# pixracer_power.net
KiCad netlist of a schematic drawn in Altium Designer
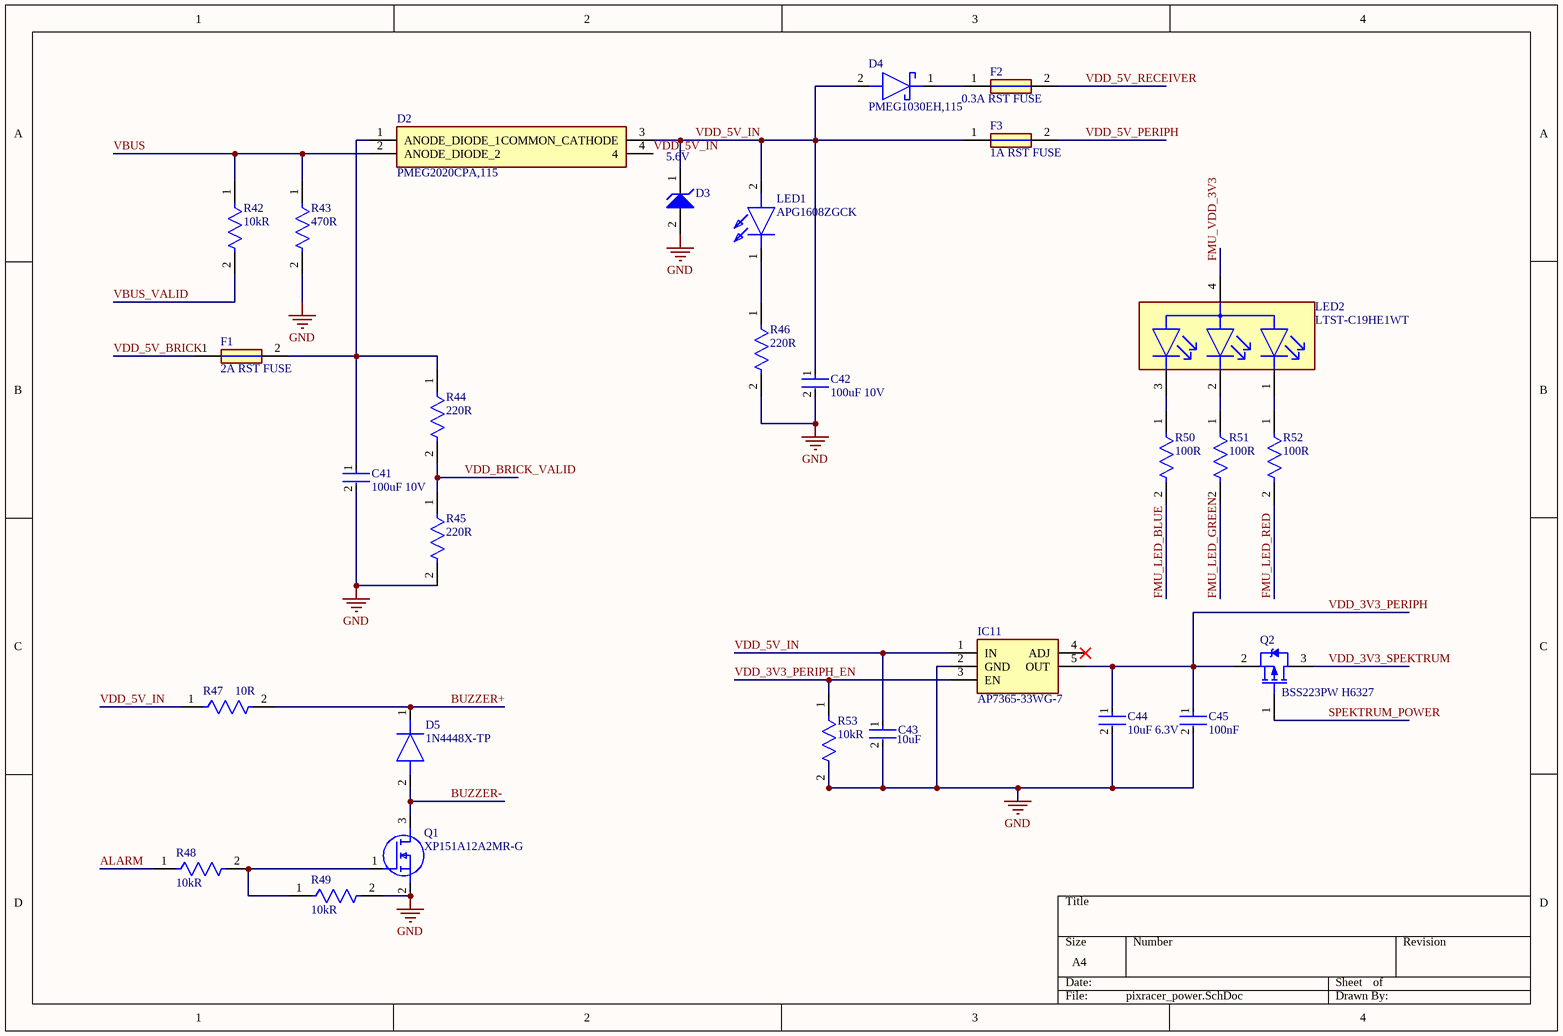
[diagram p0: pixracer_power.SchDoc]

(export (version "E")
  (design (tool "Eeschema 10.0.6"))
  (components
    (comp (ref "C41")
      (value "C3216X5R1A107M160AC")
      (footprint "FP-C3216-160-0_3-IPC_C")
      (description "Multilayer Ceramic Capacitors 100uF ±20% 10V X5R SMD 1206")
      (fields
        (field (name "CAPACITANCE") "100uF 10V")
        (field (name "VOLTAGE") "10V")
        (field (name "TOLERANCE") "20%")
      )
      (libsource (lib "Altium Content Vault") (part "02cd4be3c70576c341d710602a673aa"))
    )
    (comp (ref "C42")
      (value "C3216X5R1A107M160AC")
      (footprint "FP-C3216-160-0_3-IPC_C")
      (description "Multilayer Ceramic Capacitors 100uF ±20% 10V X5R SMD 1206")
      (fields
        (field (name "CAPACITANCE") "100uF 10V")
        (field (name "VOLTAGE") "10V")
        (field (name "TOLERANCE") "20%")
      )
      (libsource (lib "Altium Content Vault") (part "02cd4be3c70576c341d710602a673aa"))
    )
    (comp (ref "C43")
      (value "CL10A106KP8NNND")
      (footprint "FP-CL10-IPC_B")
      (description "Cap Ceramic 10uF 10V X5R ±10% Pad SMD 0603 +85°C T/R")
      (fields (field (name "TOLERANCE") "10%") (field (name "CAPACITANCE") "10uF"))
      (libsource (lib "Altium Content Vault") (part "b4654b650e69147ec39a6b967a45e02"))
    )
    (comp (ref "C44")
      (value "CC0603KRX5R5BB106")
      (footprint "FP-CC0603-0_15-0_95-IPC_B")
      (description "CAP CER 10UF 6.3V X5R 0603")
      (fields
        (field (name "TOLERANCE") "20%")
        (field (name "CAPACITANCE") "10uF 6.3V")
        (field (name "VOLTAGE") "4V")
      )
      (libsource (lib "Altium Content Vault") (part "02cd4be3c70576c341d710602a673aa"))
    )
    (comp (ref "C45")
      (value "0603ZC104MAT2A")
      (footprint "FP-0603-L_1_6_0_15-W_0_81-IPC_B")
      (description "General Purpose Ceramic Capacitor, 0603, 100nF, 20%, X7R, 15%, 10V")
      (fields (field (name "TOLERANCE") "20%") (field (name "CAPACITANCE") "100nF"))
      (libsource (lib "Altium Content Vault") (part "02cd4be3c70576c341d710602a673aa"))
    )
    (comp (ref "D2")
      (value "PMEG2020CPA,115")
      (footprint "SamacSys:PMEG2020CPA115")
      (description "Schottky Diode")
      (fields (field (name "MOUSER PART NUMBER") "771-PMEG2020CPA115"))
      (libsource (lib "*") (part "PMEG2020CPA,115"))
    )
    (comp (ref "D3")
      (value "MMSZ5232BT1G")
      (footprint "ONSC-SOD-123-2-425-04_V")
      (description "Zener Voltage Regulator, 500 mW, 2-Pin SOD-123, Pb-Free, Tape and Reel")
      (fields (field (name "MANUFACTURER") "On Semiconductor") (field (name "VZ TYP (V)") "5.6V"))
      (libsource (lib "Altium Content Vault") (part "ONSC-K1A2-2"))
    )
    (comp (ref "D4")
      (value "PMEG1030EH,115")
      (footprint "SamacSys:SODFL3516X120N")
      (description "Schottky Diode")
      (libsource (lib "*") (part "PMEG1030EH,115"))
    )
    (comp (ref "D5")
      (value "1N4448X-TP")
      (footprint "SamacSys:1N4448XTP")
      (description "Diode")
      (fields (field (name "MOUSER PART NUMBER") "833-1N4448X-TP"))
      (libsource (lib "*") (part "1N4448X-TP"))
    )
    (comp (ref "F1")
      (value "2A RST FUSE")
      (footprint "SamacSys:FUSC3216X100N")
      (description "Fuse")
      (fields
        (field (name "MANUFACTURER_PART_NUMBER") "0ZCJ0100FF2E")
        (field (name "MOUSER PART NUMBER") "530-0ZCJ0100FF2E")
      )
      (libsource (lib "*") (part "0ZCJ0100FF2E"))
    )
    (comp (ref "F2")
      (value "0.3A RST FUSE")
      (footprint "SamacSys:FUSC2214X75N")
      (description "Fuse")
      (fields
        (field (name "MANUFACTURER_PART_NUMBER") "0ZCK0035FF2G")
        (field (name "MOUSER PART NUMBER") "530-0ZCK0035FF2G")
      )
      (libsource (lib "*") (part "0ZCK0035FF2G"))
    )
    (comp (ref "F3")
      (value "1A RST FUSE")
      (footprint "SamacSys:FUSC3216X100N")
      (description "Fuse")
      (fields
        (field (name "MANUFACTURER_PART_NUMBER") "0ZCJ0100FF2E")
        (field (name "MOUSER PART NUMBER") "530-0ZCJ0100FF2E")
      )
      (libsource (lib "*") (part "0ZCJ0100FF2E"))
    )
    (comp (ref "IC11")
      (value "AP7365-33WG-7")
      (footprint "SamacSys:SOT95P285X130-5N")
      (description "Integrated Circuit")
      (fields (field (name "MOUSER PART NUMBER") "621-AP7365-33WG-7"))
      (libsource (lib "*") (part "AP7365-33WG-7"))
    )
    (comp (ref "LED1")
      (value "APG1608ZGCK")
      (footprint "SamacSys:LEDC1608X28N")
      (description "LED")
      (fields (field (name "MOUSER PART NUMBER") "604-APG1608ZGCK"))
      (libsource (lib "*") (part "APG1608ZGCK"))
    )
    (comp (ref "LED2")
      (value "LTST-C19HE1WT")
      (footprint "FP-LTST-C19HE1WT-MFG")
      (description "LED RGB DIFFUSED CHIP SMD")
      (libsource (lib "Altium Content Vault") (part "2c4e1fdd461916b293eda504ca5a2b6"))
    )
    (comp (ref "Q1")
      (value "XP151A12A2MR-G")
      (footprint "SamacSys:SOT95P280X130-3N")
      (description "MOSFET (N-Channel)")
      (fields (field (name "MOUSER PART NUMBER") "865-XP151A12A2MR-G"))
      (libsource (lib "*") (part "XP151A12A2MR-G"))
    )
    (comp (ref "Q2")
      (value "BSS223PW H6327")
      (footprint "INF-PG-SOT-323_N")
      (fields (field (name "MANUFACTURER") "Infineon"))
      (libsource (lib "Altium Content Vault") (part "INF-PEMOS-GSD-3-B"))
    )
    (comp (ref "R42")
      (value "ERJ-3GEYJ103V")
      (footprint "FP-ERJ3G-IPC_C")
      (description "RES SMD 10K OHM 5% 1/10W 0603")
      (fields (field (name "TOLERANCE") "5%") (field (name "RESISTANCE") "10kR"))
      (libsource (lib "Altium Content Vault") (part "1029c3af85768c4190bb7ad29bc67b5"))
    )
    (comp (ref "R43")
      (value "CRCW0603470RJNEA")
      (footprint "FP-CRCW0603-e3-IPC_A")
      (description "RES Thick Film, 470Ω, 5%, 0.1W, 200ppm/°C, 0603")
      (fields (field (name "RESISTANCE") "470R") (field (name "TOLERANCE") "5%"))
      (libsource (lib "Altium Content Vault") (part "1029c3af85768c4190bb7ad29bc67b5"))
    )
    (comp (ref "R44")
      (value "CRCW0603220RFKEB")
      (footprint "FP-CRCW0603-e3-MFG")
      (description "RES Thick Film, 220Ω, 1%, 0.1W, 100ppm/°C, 0603")
      (fields (field (name "TOLERANCE") "1%") (field (name "RESISTANCE") "220R"))
      (libsource (lib "Altium Content Vault") (part "1029c3af85768c4190bb7ad29bc67b5"))
    )
    (comp (ref "R45")
      (value "CRCW0603220RFKEB")
      (footprint "FP-CRCW0603-e3-MFG")
      (description "RES Thick Film, 220Ω, 1%, 0.1W, 100ppm/°C, 0603")
      (fields (field (name "TOLERANCE") "1%") (field (name "RESISTANCE") "220R"))
      (libsource (lib "Altium Content Vault") (part "1029c3af85768c4190bb7ad29bc67b5"))
    )
    (comp (ref "R46")
      (value "CRCW0603220RFKEB")
      (footprint "FP-CRCW0603-e3-MFG")
      (description "RES Thick Film, 220Ω, 1%, 0.1W, 100ppm/°C, 0603")
      (fields (field (name "TOLERANCE") "1%") (field (name "RESISTANCE") "220R"))
      (libsource (lib "Altium Content Vault") (part "1029c3af85768c4190bb7ad29bc67b5"))
    )
    (comp (ref "R47")
      (value "10R")
      (footprint "FP-RT0603-MFG")
      (description "RES SMD 10 OHM 0.1% 1/10W 0603")
      (fields (field (name "TOLERANCE") "0.001") (field (name "MANUFACTURER") "Yageo"))
      (libsource (lib "Altium Content Vault") (part "1029c3af85768c4190bb7ad29bc67b5"))
    )
    (comp (ref "R48")
      (value "ERJ-3GEYJ103V")
      (footprint "FP-ERJ3G-IPC_C")
      (description "RES SMD 10K OHM 5% 1/10W 0603")
      (fields (field (name "TOLERANCE") "5%") (field (name "RESISTANCE") "10kR"))
      (libsource (lib "Altium Content Vault") (part "1029c3af85768c4190bb7ad29bc67b5"))
    )
    (comp (ref "R49")
      (value "ERJ-3GEYJ103V")
      (footprint "FP-ERJ3G-IPC_C")
      (description "RES SMD 10K OHM 5% 1/10W 0603")
      (fields (field (name "TOLERANCE") "5%") (field (name "RESISTANCE") "10kR"))
      (libsource (lib "Altium Content Vault") (part "1029c3af85768c4190bb7ad29bc67b5"))
    )
    (comp (ref "R50")
      (value "CRCW0603100RFKEB")
      (footprint "FP-CRCW0603-e3-IPC_A")
      (description "RES Thick Film, 100Ω, 1%, 0.1W, 100ppm/°C, 0603")
      (fields (field (name "TOLERANCE") "1%") (field (name "RESISTANCE") "100R"))
      (libsource (lib "Altium Content Vault") (part "1029c3af85768c4190bb7ad29bc67b5"))
    )
    (comp (ref "R51")
      (value "CRCW0603100RFKEB")
      (footprint "FP-CRCW0603-e3-IPC_A")
      (description "RES Thick Film, 100Ω, 1%, 0.1W, 100ppm/°C, 0603")
      (fields (field (name "TOLERANCE") "1%") (field (name "RESISTANCE") "100R"))
      (libsource (lib "Altium Content Vault") (part "1029c3af85768c4190bb7ad29bc67b5"))
    )
    (comp (ref "R52")
      (value "CRCW0603100RFKEB")
      (footprint "FP-CRCW0603-e3-IPC_A")
      (description "RES Thick Film, 100Ω, 1%, 0.1W, 100ppm/°C, 0603")
      (fields (field (name "TOLERANCE") "1%") (field (name "RESISTANCE") "100R"))
      (libsource (lib "Altium Content Vault") (part "1029c3af85768c4190bb7ad29bc67b5"))
    )
    (comp (ref "R53")
      (value "ERJ-3GEYJ103V")
      (footprint "FP-ERJ3G-IPC_C")
      (description "RES SMD 10K OHM 5% 1/10W 0603")
      (fields (field (name "TOLERANCE") "5%") (field (name "RESISTANCE") "10kR"))
      (libsource (lib "Altium Content Vault") (part "1029c3af85768c4190bb7ad29bc67b5"))
    )
  )
  (nets
    (net (code "1") (name "/ALARM") (class "Default")
      (node (ref "R48") (pin "1") (pinfunction "1_1") (pintype "passive"))
    )
    (net (code "2") (name "/BUZZER+") (class "Default")
      (node (ref "D5") (pin "1") (pinfunction "K_1") (pintype "passive"))
      (node (ref "R47") (pin "2") (pinfunction "2_2") (pintype "passive"))
    )
    (net (code "3") (name "/BUZZER-") (class "Default")
      (node (ref "D5") (pin "2") (pinfunction "A_2") (pintype "passive"))
      (node (ref "Q1") (pin "3") (pinfunction "D_3") (pintype "passive"))
    )
    (net (code "4") (name "/FMU_LED_BLUE") (class "Default")
      (node (ref "R50") (pin "2") (pinfunction "2_2") (pintype "passive"))
    )
    (net (code "5") (name "/FMU_LED_GREEN") (class "Default")
      (node (ref "R51") (pin "2") (pinfunction "2_2") (pintype "passive"))
    )
    (net (code "6") (name "/FMU_LED_RED") (class "Default")
      (node (ref "R52") (pin "2") (pinfunction "2_2") (pintype "passive"))
    )
    (net (code "7") (name "/FMU_VDD_3V3") (class "Default")
      (node (ref "LED2") (pin "4") (pinfunction "A_4") (pintype "passive"))
    )
    (net (code "8") (name "/SPEKTRUM_POWER") (class "Default")
      (node (ref "Q2") (pin "1") (pinfunction "GATE_1") (pintype "passive"))
    )
    (net (code "9") (name "/VBUS") (class "Default")
      (node (ref "D2") (pin "2") (pinfunction "ANODE_DIODE_2_2") (pintype "passive"))
      (node (ref "R42") (pin "1") (pinfunction "1_1") (pintype "passive"))
      (node (ref "R43") (pin "1") (pinfunction "1_1") (pintype "passive"))
    )
    (net (code "10") (name "/VBUS_VALID") (class "Default")
      (node (ref "R42") (pin "2") (pinfunction "2_2") (pintype "passive"))
    )
    (net (code "11") (name "/VDD_3V3_PERIPH") (class "Default")
      (node (ref "C44") (pin "1") (pinfunction "1_1") (pintype "passive"))
      (node (ref "C45") (pin "1") (pinfunction "1_1") (pintype "passive"))
      (node (ref "IC11") (pin "5") (pinfunction "OUT_5") (pintype "passive"))
      (node (ref "Q2") (pin "2") (pinfunction "SOURCE_2") (pintype "passive"))
    )
    (net (code "12") (name "/VDD_3V3_PERIPH_EN") (class "Default")
      (node (ref "IC11") (pin "3") (pinfunction "EN_3") (pintype "passive"))
      (node (ref "R53") (pin "1") (pinfunction "1_1") (pintype "passive"))
    )
    (net (code "13") (name "/VDD_3V3_SPEKTRUM") (class "Default")
      (node (ref "Q2") (pin "3") (pinfunction "DRAIN_3") (pintype "passive"))
    )
    (net (code "14") (name "/VDD_5V_BRICK") (class "Default")
      (node (ref "F1") (pin "1") (pinfunction "1_1") (pintype "passive"))
    )
    (net (code "15") (name "/VDD_5V_IN") (class "Default")
      (node (ref "C42") (pin "1") (pinfunction "1_1") (pintype "passive"))
      (node (ref "C43") (pin "1") (pinfunction "1_1") (pintype "passive"))
      (node (ref "D2") (pin "3") (pinfunction "COMMON_CATHODE_3") (pintype "passive"))
      (node (ref "D2") (pin "4") (pinfunction "4_4") (pintype "passive"))
      (node (ref "D3") (pin "1") (pinfunction "K_1") (pintype "passive"))
      (node (ref "D4") (pin "2") (pinfunction "A_2") (pintype "passive"))
      (node (ref "F3") (pin "1") (pinfunction "1_1") (pintype "passive"))
      (node (ref "IC11") (pin "1") (pinfunction "IN_1") (pintype "passive"))
      (node (ref "LED1") (pin "2") (pinfunction "A_2") (pintype "passive"))
      (node (ref "R47") (pin "1") (pinfunction "1_1") (pintype "passive"))
    )
    (net (code "16") (name "/VDD_5V_PERIPH") (class "Default")
      (node (ref "F3") (pin "2") (pinfunction "2_2") (pintype "passive"))
    )
    (net (code "17") (name "/VDD_5V_RECEIVER") (class "Default")
      (node (ref "F2") (pin "2") (pinfunction "2_2") (pintype "passive"))
    )
    (net (code "18") (name "/VDD_BRICK_VALID") (class "Default")
      (node (ref "R44") (pin "2") (pinfunction "2_2") (pintype "passive"))
      (node (ref "R45") (pin "1") (pinfunction "1_1") (pintype "passive"))
    )
    (net (code "19") (name "GND") (class "Default")
      (node (ref "C41") (pin "2") (pinfunction "2_2") (pintype "passive"))
      (node (ref "C42") (pin "2") (pinfunction "2_2") (pintype "passive"))
      (node (ref "C43") (pin "2") (pinfunction "2_2") (pintype "passive"))
      (node (ref "C44") (pin "2") (pinfunction "2_2") (pintype "passive"))
      (node (ref "C45") (pin "2") (pinfunction "2_2") (pintype "passive"))
      (node (ref "D3") (pin "2") (pinfunction "A_2") (pintype "passive"))
      (node (ref "IC11") (pin "2") (pinfunction "GND_2") (pintype "passive"))
      (node (ref "Q1") (pin "2") (pinfunction "S_2") (pintype "passive"))
      (node (ref "R43") (pin "2") (pinfunction "2_2") (pintype "passive"))
      (node (ref "R45") (pin "2") (pinfunction "2_2") (pintype "passive"))
      (node (ref "R46") (pin "2") (pinfunction "2_2") (pintype "passive"))
      (node (ref "R49") (pin "2") (pinfunction "2_2") (pintype "passive"))
      (node (ref "R53") (pin "2") (pinfunction "2_2") (pintype "passive"))
    )
    (net (code "20") (name "Net-(D2-ANODE_DIODE_1)") (class "Default")
      (node (ref "C41") (pin "1") (pinfunction "1_1") (pintype "passive"))
      (node (ref "D2") (pin "1") (pinfunction "ANODE_DIODE_1_1") (pintype "passive"))
      (node (ref "F1") (pin "2") (pinfunction "2_2") (pintype "passive"))
      (node (ref "R44") (pin "1") (pinfunction "1_1") (pintype "passive"))
    )
    (net (code "21") (name "Net-(D4-K)") (class "Default")
      (node (ref "D4") (pin "1") (pinfunction "K_1") (pintype "passive"))
      (node (ref "F2") (pin "1") (pinfunction "1_1") (pintype "passive"))
    )
    (net (code "22") (name "Net-(LED1-K)") (class "Default")
      (node (ref "LED1") (pin "1") (pinfunction "K_1") (pintype "passive"))
      (node (ref "R46") (pin "1") (pinfunction "1_1") (pintype "passive"))
    )
    (net (code "23") (name "Net-(LED2-BLUE_C)") (class "Default")
      (node (ref "LED2") (pin "3") (pinfunction "BLUE_C_3") (pintype "passive"))
      (node (ref "R50") (pin "1") (pinfunction "1_1") (pintype "passive"))
    )
    (net (code "24") (name "Net-(LED2-GREEN_C)") (class "Default")
      (node (ref "LED2") (pin "2") (pinfunction "GREEN_C_2") (pintype "passive"))
      (node (ref "R51") (pin "1") (pinfunction "1_1") (pintype "passive"))
    )
    (net (code "25") (name "Net-(LED2-RED_C)") (class "Default")
      (node (ref "LED2") (pin "1") (pinfunction "RED_C_1") (pintype "passive"))
      (node (ref "R52") (pin "1") (pinfunction "1_1") (pintype "passive"))
    )
    (net (code "26") (name "Net-(Q1-G)") (class "Default")
      (node (ref "Q1") (pin "1") (pinfunction "G_1") (pintype "passive"))
      (node (ref "R48") (pin "2") (pinfunction "2_2") (pintype "passive"))
      (node (ref "R49") (pin "1") (pinfunction "1_1") (pintype "passive"))
    )
    (net (code "27") (name "unconnected-(IC11-ADJ-Pad4)") (class "Default")
      (node (ref "IC11") (pin "4") (pinfunction "ADJ_4") (pintype "passive+no_connect"))
    )
  )
)
